# ESP8266_Wiring.net
KiCad netlist of a schematic drawn in EAGLE
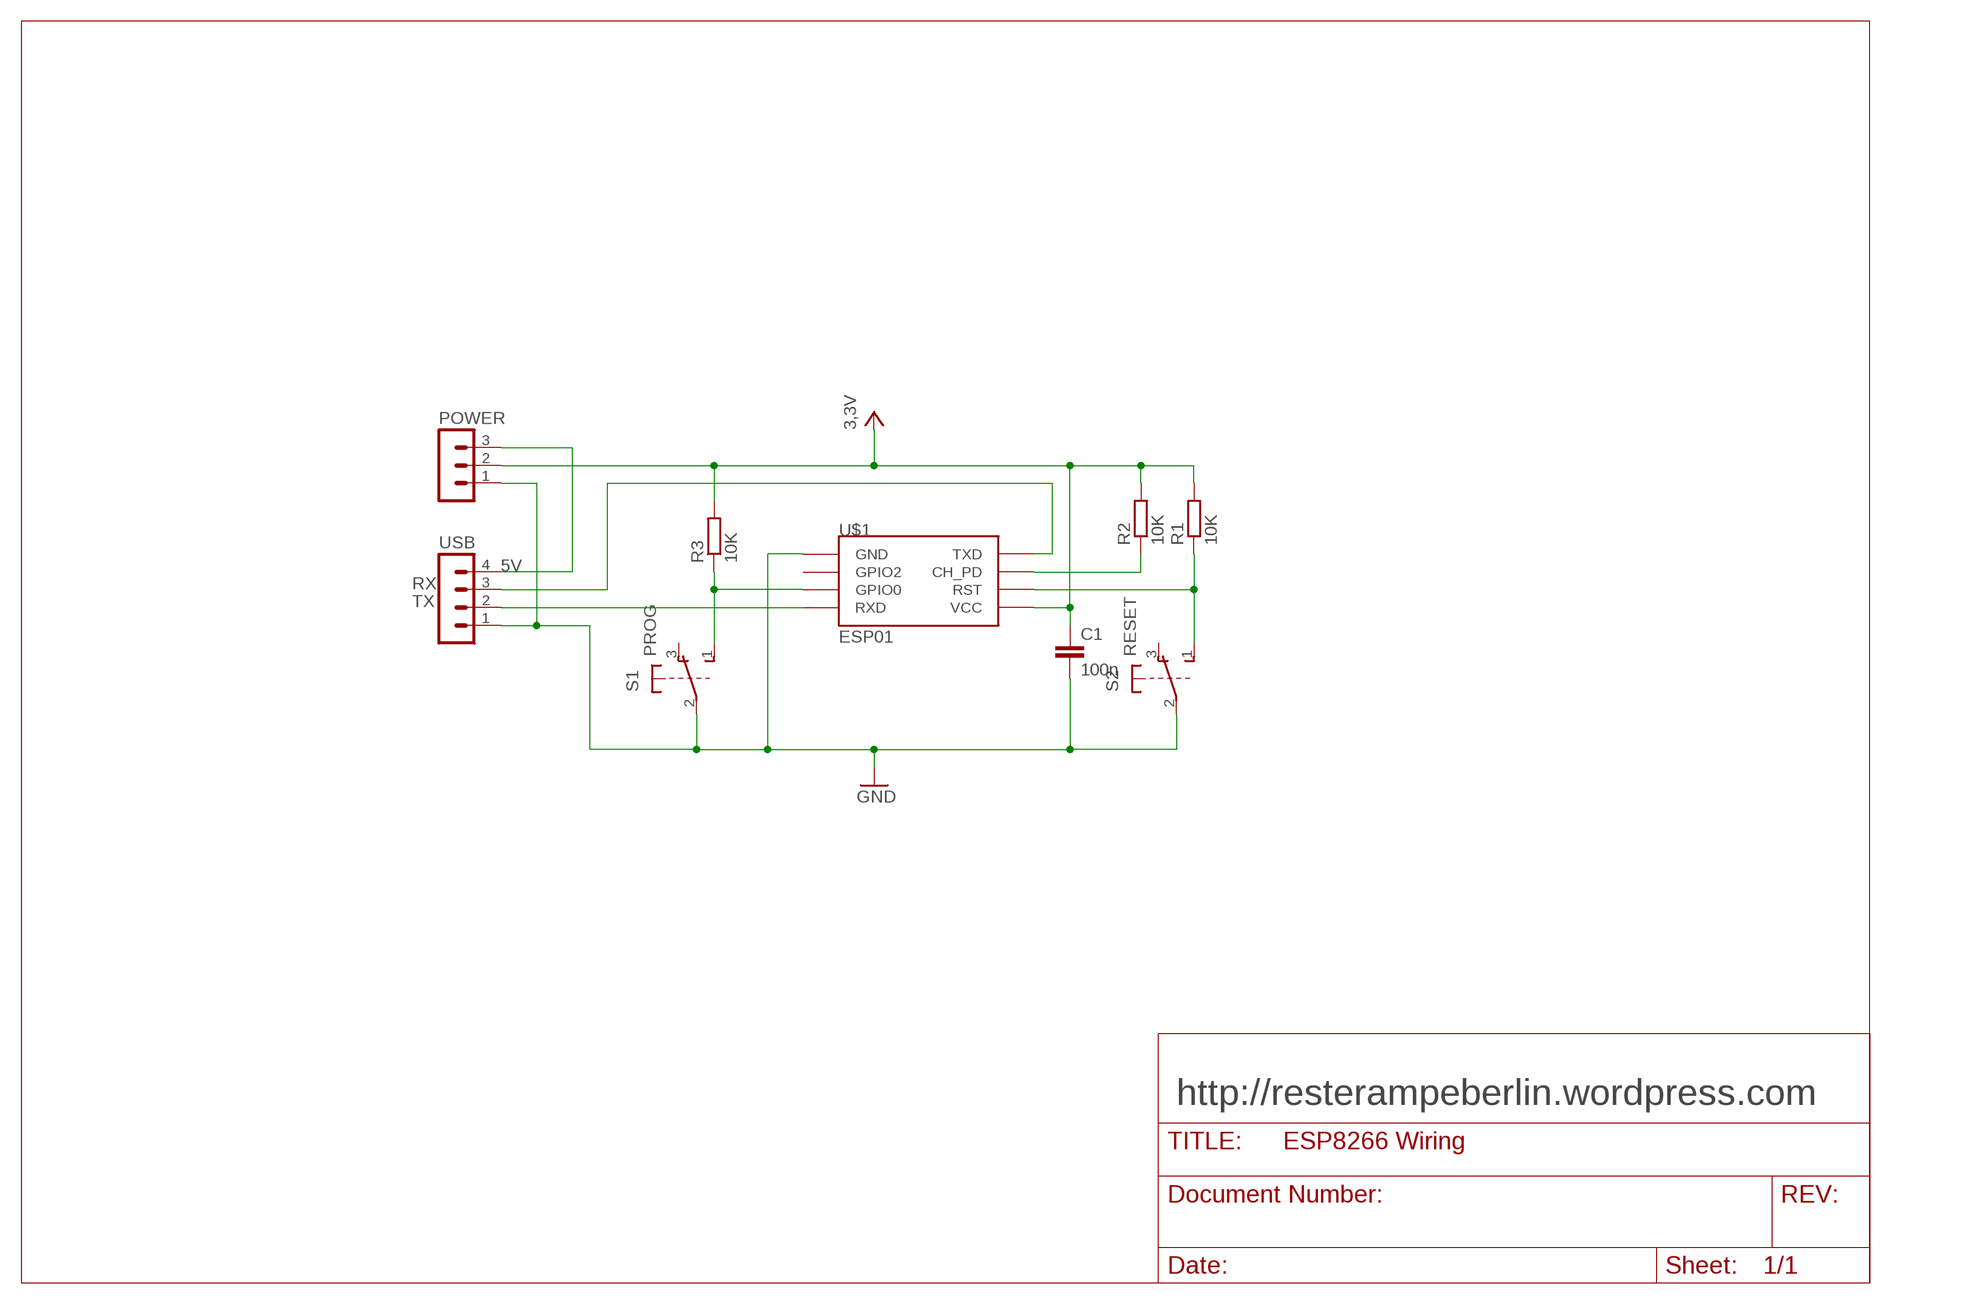
[diagram p0: schematic, sheet 1]

(export (version "E")
  (design (tool "Eeschema 10.0.6"))
  (components
    (comp (ref "C1")
      (value "100n")
      (footprint "eagle-import:C5B3")
      (libsource (lib "eagle-import") (part "C5/3"))
    )
    (comp (ref "POWER")
      (value "MA03-1")
      (footprint "eagle-import:MA03-1")
      (libsource (lib "eagle-import") (part "MA03-1"))
    )
    (comp (ref "R1")
      (value "10K")
      (footprint "eagle-import:0207_10")
      (libsource (lib "eagle-import") (part "R-EU_0207/10"))
    )
    (comp (ref "R2")
      (value "10K")
      (footprint "eagle-import:0207_10")
      (libsource (lib "eagle-import") (part "R-EU_0207/10"))
    )
    (comp (ref "R3")
      (value "10K")
      (footprint "eagle-import:0207_10")
      (libsource (lib "eagle-import") (part "R-EU_0207/10"))
    )
    (comp (ref "S1")
      (value "PROG")
      (footprint "eagle-import:9077-2")
      (libsource (lib "eagle-import") (part "9077-2"))
    )
    (comp (ref "S2")
      (value "RESET")
      (footprint "eagle-import:9077-2")
      (libsource (lib "eagle-import") (part "9077-2"))
    )
    (comp (ref "U$1")
      (value "ESP01")
      (footprint "eagle-import:ESP01")
      (libsource (lib "eagle-import") (part "ESP01"))
    )
    (comp (ref "USB")
      (value "MA04-1")
      (footprint "eagle-import:MA04-1")
      (libsource (lib "eagle-import") (part "MA04-1"))
    )
  )
  (nets
    (net (code "1") (name "/5V") (class "Default")
      (node (ref "POWER") (pin "3") (pinfunction "3_3") (pintype "passive"))
      (node (ref "USB") (pin "4") (pinfunction "4_4") (pintype "passive"))
    )
    (net (code "2") (name "3,3V") (class "Default")
      (node (ref "C1") (pin "1") (pinfunction "1_1") (pintype "passive"))
      (node (ref "POWER") (pin "2") (pinfunction "2_2") (pintype "passive"))
      (node (ref "R1") (pin "2") (pinfunction "2_2") (pintype "passive"))
      (node (ref "R2") (pin "2") (pinfunction "2_2") (pintype "passive"))
      (node (ref "R3") (pin "2") (pinfunction "2_2") (pintype "passive"))
      (node (ref "U$1") (pin "VCC") (pinfunction "VCC_VCC") (pintype "bidirectional"))
    )
    (net (code "3") (name "GND") (class "Default")
      (node (ref "C1") (pin "2") (pinfunction "2_2") (pintype "passive"))
      (node (ref "POWER") (pin "1") (pinfunction "1_1") (pintype "passive"))
      (node (ref "S1") (pin "2") (pinfunction "P_2") (pintype "passive"))
      (node (ref "S2") (pin "2") (pinfunction "P_2") (pintype "passive"))
      (node (ref "U$1") (pin "GND") (pinfunction "GND_GND") (pintype "bidirectional"))
      (node (ref "USB") (pin "1") (pinfunction "1_1") (pintype "passive"))
    )
    (net (code "4") (name "Net-(R2-Pad1)") (class "Default")
      (node (ref "R2") (pin "1") (pinfunction "1_1") (pintype "passive"))
      (node (ref "U$1") (pin "CH_PD") (pinfunction "CH_PD_CH_PD") (pintype "bidirectional"))
    )
    (net (code "5") (name "Net-(S1A-S)") (class "Default")
      (node (ref "R3") (pin "1") (pinfunction "1_1") (pintype "passive"))
      (node (ref "S1") (pin "1") (pinfunction "S_1") (pintype "passive"))
      (node (ref "U$1") (pin "GPIO0") (pinfunction "GPIO0_GPIO0") (pintype "bidirectional"))
    )
    (net (code "6") (name "Net-(S2A-S)") (class "Default")
      (node (ref "R1") (pin "1") (pinfunction "1_1") (pintype "passive"))
      (node (ref "S2") (pin "1") (pinfunction "S_1") (pintype "passive"))
      (node (ref "U$1") (pin "RST") (pinfunction "RST_RST") (pintype "bidirectional"))
    )
    (net (code "7") (name "Net-(U$1-RXD)") (class "Default")
      (node (ref "U$1") (pin "RX") (pinfunction "RXD_RX") (pintype "bidirectional"))
      (node (ref "USB") (pin "2") (pinfunction "2_2") (pintype "passive"))
    )
    (net (code "8") (name "Net-(U$1-TXD)") (class "Default")
      (node (ref "U$1") (pin "TX") (pinfunction "TXD_TX") (pintype "bidirectional"))
      (node (ref "USB") (pin "3") (pinfunction "3_3") (pintype "passive"))
    )
    (net (code "9") (name "unconnected-(S1A-O-Pad3)") (class "Default")
      (node (ref "S1") (pin "3") (pinfunction "O_3") (pintype "passive"))
    )
    (net (code "10") (name "unconnected-(S2A-O-Pad3)") (class "Default")
      (node (ref "S2") (pin "3") (pinfunction "O_3") (pintype "passive"))
    )
    (net (code "11") (name "unconnected-(U$1-PadGPIO2)") (class "Default")
      (node (ref "U$1") (pin "GPIO2") (pinfunction "GPIO2_GPIO2") (pintype "bidirectional"))
    )
  )
)
